# mosfet_x4.net
KiCad netlist of a schematic drawn in EAGLE
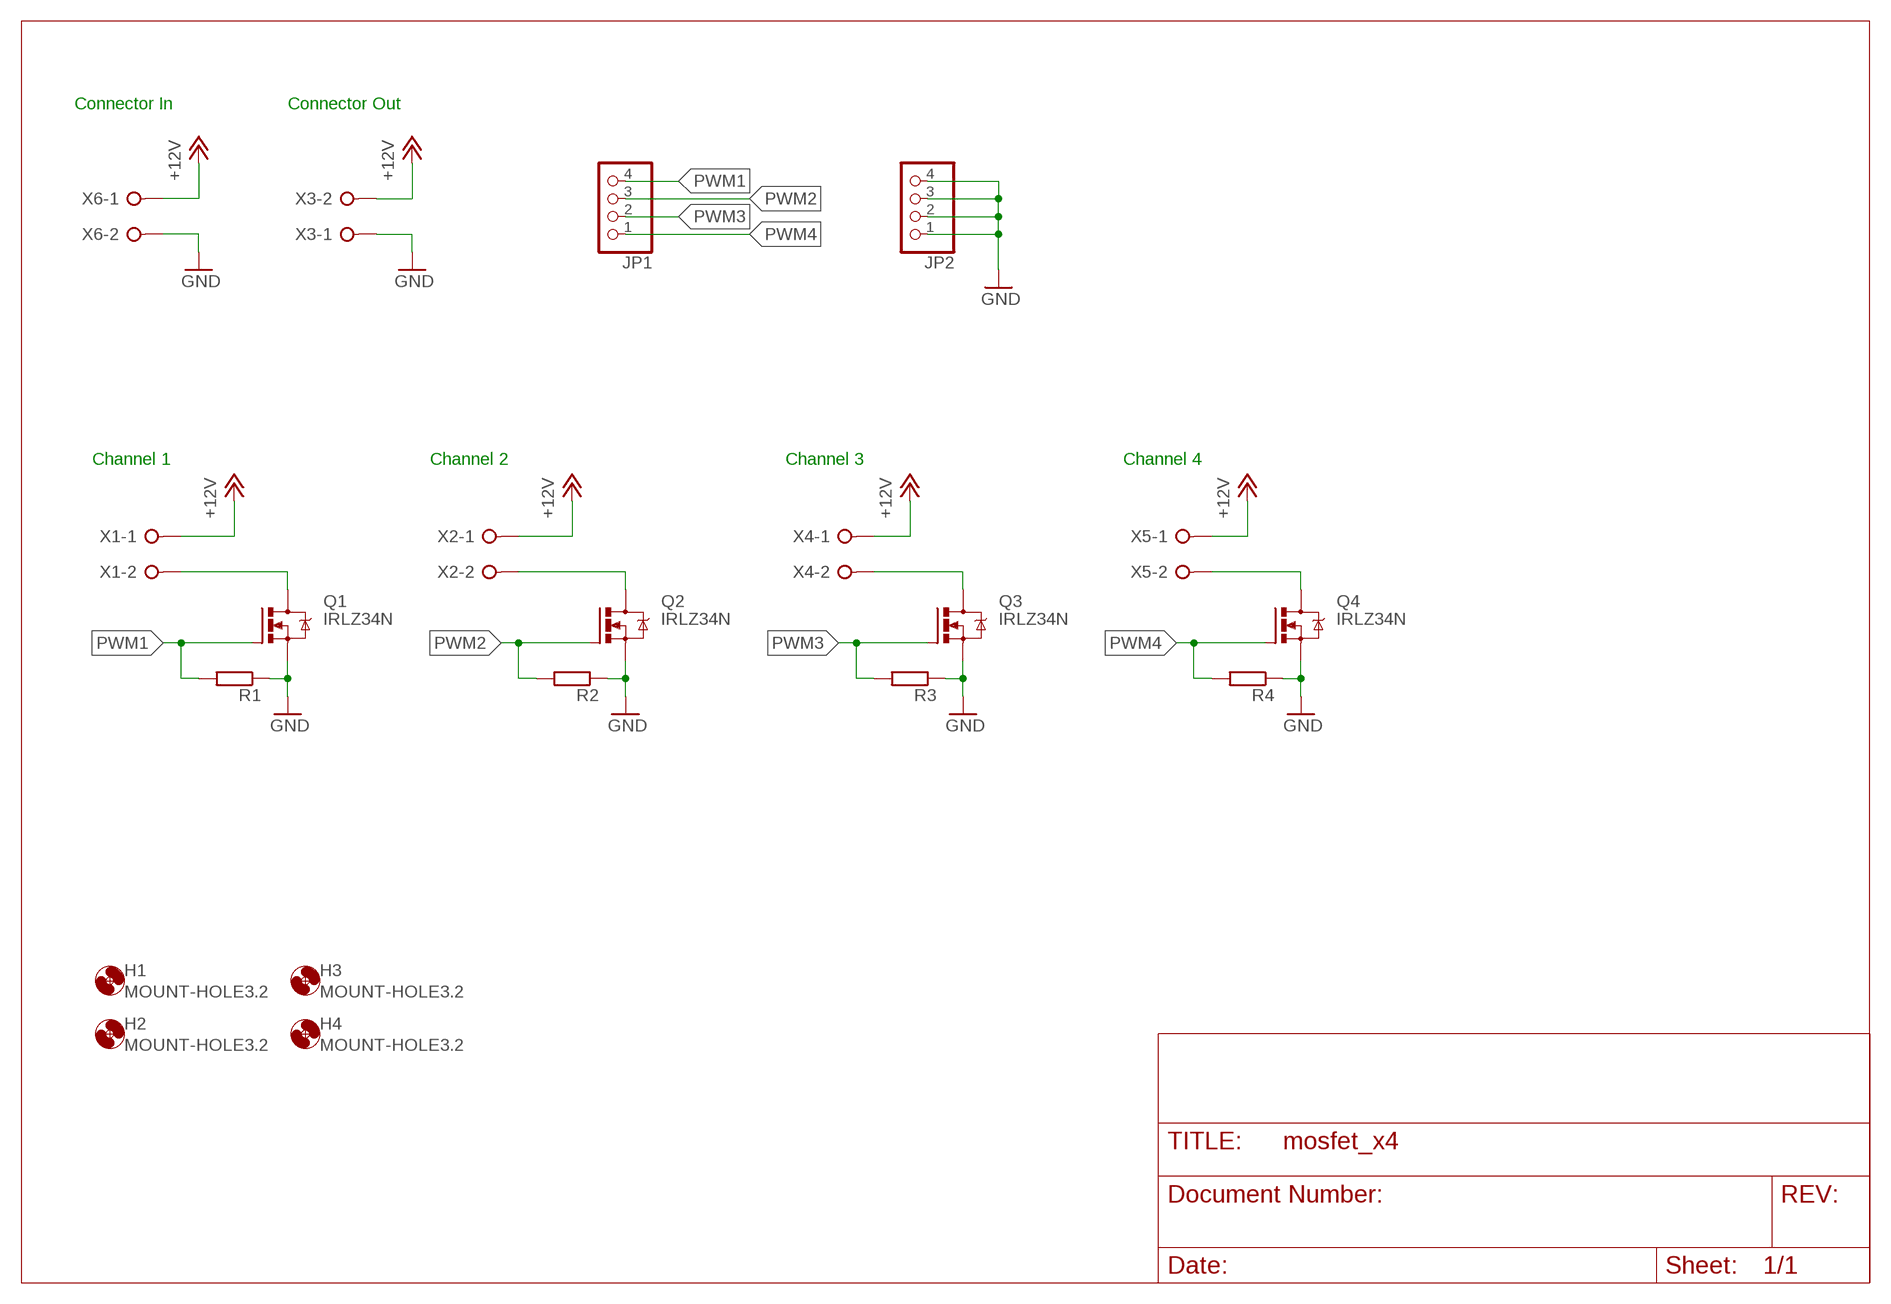
[diagram p0: schematic, sheet 1]

(export (version "E")
  (design (tool "Eeschema 10.0.6"))
  (components
    (comp (ref "H1")
      (value "MOUNT-HOLE3.2")
      (footprint "eagle-import:3,2")
      (libsource (lib "eagle-import") (part "MOUNT-HOLE3.2"))
    )
    (comp (ref "H2")
      (value "MOUNT-HOLE3.2")
      (footprint "eagle-import:3,2")
      (libsource (lib "eagle-import") (part "MOUNT-HOLE3.2"))
    )
    (comp (ref "H3")
      (value "MOUNT-HOLE3.2")
      (footprint "eagle-import:3,2")
      (libsource (lib "eagle-import") (part "MOUNT-HOLE3.2"))
    )
    (comp (ref "H4")
      (value "MOUNT-HOLE3.2")
      (footprint "eagle-import:3,2")
      (libsource (lib "eagle-import") (part "MOUNT-HOLE3.2"))
    )
    (comp (ref "JP1")
      (value "PINHD-1X4")
      (footprint "eagle-import:1X04")
      (libsource (lib "eagle-import") (part "PINHD-1X4"))
    )
    (comp (ref "JP2")
      (value "PINHD-1X4")
      (footprint "eagle-import:1X04")
      (libsource (lib "eagle-import") (part "PINHD-1X4"))
    )
    (comp (ref "Q1")
      (value "IRLZ34N")
      (footprint "eagle-import:TO220BV")
      (libsource (lib "eagle-import") (part "IRLZ44ZTO220BV"))
    )
    (comp (ref "Q2")
      (value "IRLZ34N")
      (footprint "eagle-import:TO220BV")
      (libsource (lib "eagle-import") (part "IRLZ44ZTO220BV"))
    )
    (comp (ref "Q3")
      (value "IRLZ34N")
      (footprint "eagle-import:TO220BV")
      (libsource (lib "eagle-import") (part "IRLZ44ZTO220BV"))
    )
    (comp (ref "Q4")
      (value "IRLZ34N")
      (footprint "eagle-import:TO220BV")
      (libsource (lib "eagle-import") (part "IRLZ44ZTO220BV"))
    )
    (comp (ref "R1")
      (value "R-EU_0207/10")
      (footprint "eagle-import:0207_10")
      (libsource (lib "eagle-import") (part "R-EU_0207/10"))
    )
    (comp (ref "R2")
      (value "R-EU_0207/10")
      (footprint "eagle-import:0207_10")
      (libsource (lib "eagle-import") (part "R-EU_0207/10"))
    )
    (comp (ref "R3")
      (value "R-EU_0207/10")
      (footprint "eagle-import:0207_10")
      (libsource (lib "eagle-import") (part "R-EU_0207/10"))
    )
    (comp (ref "R4")
      (value "R-EU_0207/10")
      (footprint "eagle-import:0207_10")
      (libsource (lib "eagle-import") (part "R-EU_0207/10"))
    )
    (comp (ref "X1")
      (value "W237-02P")
      (footprint "eagle-import:W237-132")
      (libsource (lib "eagle-import") (part "W237-02P"))
    )
    (comp (ref "X2")
      (value "W237-02P")
      (footprint "eagle-import:W237-132")
      (libsource (lib "eagle-import") (part "W237-02P"))
    )
    (comp (ref "X3")
      (value "W237-02P")
      (footprint "eagle-import:W237-132")
      (libsource (lib "eagle-import") (part "W237-02P"))
    )
    (comp (ref "X4")
      (value "W237-02P")
      (footprint "eagle-import:W237-132")
      (libsource (lib "eagle-import") (part "W237-02P"))
    )
    (comp (ref "X5")
      (value "W237-02P")
      (footprint "eagle-import:W237-132")
      (libsource (lib "eagle-import") (part "W237-02P"))
    )
    (comp (ref "X6")
      (value "W237-02P")
      (footprint "eagle-import:W237-132")
      (libsource (lib "eagle-import") (part "W237-02P"))
    )
  )
  (nets
    (net (code "1") (name "+12V") (class "Default")
      (node (ref "X1") (pin "1") (pinfunction "KL_1") (pintype "passive"))
      (node (ref "X2") (pin "1") (pinfunction "KL_1") (pintype "passive"))
      (node (ref "X3") (pin "2") (pinfunction "KL_2") (pintype "passive"))
      (node (ref "X4") (pin "1") (pinfunction "KL_1") (pintype "passive"))
      (node (ref "X5") (pin "1") (pinfunction "KL_1") (pintype "passive"))
      (node (ref "X6") (pin "1") (pinfunction "KL_1") (pintype "passive"))
    )
    (net (code "2") (name "GND") (class "Default")
      (node (ref "JP2") (pin "1") (pinfunction "1_1") (pintype "passive"))
      (node (ref "JP2") (pin "2") (pinfunction "2_2") (pintype "passive"))
      (node (ref "JP2") (pin "3") (pinfunction "3_3") (pintype "passive"))
      (node (ref "JP2") (pin "4") (pinfunction "4_4") (pintype "passive"))
      (node (ref "Q1") (pin "S") (pinfunction "S_S") (pintype "passive"))
      (node (ref "Q2") (pin "S") (pinfunction "S_S") (pintype "passive"))
      (node (ref "Q3") (pin "S") (pinfunction "S_S") (pintype "passive"))
      (node (ref "Q4") (pin "S") (pinfunction "S_S") (pintype "passive"))
      (node (ref "R1") (pin "1") (pinfunction "1_1") (pintype "passive"))
      (node (ref "R2") (pin "1") (pinfunction "1_1") (pintype "passive"))
      (node (ref "R3") (pin "1") (pinfunction "1_1") (pintype "passive"))
      (node (ref "R4") (pin "1") (pinfunction "1_1") (pintype "passive"))
      (node (ref "X3") (pin "1") (pinfunction "KL_1") (pintype "passive"))
      (node (ref "X6") (pin "2") (pinfunction "KL_2") (pintype "passive"))
    )
    (net (code "3") (name "Net-(X1B-KL)") (class "Default")
      (node (ref "Q1") (pin "D") (pinfunction "D_D") (pintype "passive"))
      (node (ref "X1") (pin "2") (pinfunction "KL_2") (pintype "passive"))
    )
    (net (code "4") (name "Net-(X2B-KL)") (class "Default")
      (node (ref "Q2") (pin "D") (pinfunction "D_D") (pintype "passive"))
      (node (ref "X2") (pin "2") (pinfunction "KL_2") (pintype "passive"))
    )
    (net (code "5") (name "Net-(X4B-KL)") (class "Default")
      (node (ref "Q3") (pin "D") (pinfunction "D_D") (pintype "passive"))
      (node (ref "X4") (pin "2") (pinfunction "KL_2") (pintype "passive"))
    )
    (net (code "6") (name "Net-(X5B-KL)") (class "Default")
      (node (ref "Q4") (pin "D") (pinfunction "D_D") (pintype "passive"))
      (node (ref "X5") (pin "2") (pinfunction "KL_2") (pintype "passive"))
    )
    (net (code "7") (name "PWM1") (class "Default")
      (node (ref "JP1") (pin "4") (pinfunction "4_4") (pintype "passive"))
      (node (ref "Q1") (pin "G") (pinfunction "G_G") (pintype "passive"))
      (node (ref "R1") (pin "2") (pinfunction "2_2") (pintype "passive"))
    )
    (net (code "8") (name "PWM2") (class "Default")
      (node (ref "JP1") (pin "3") (pinfunction "3_3") (pintype "passive"))
      (node (ref "Q2") (pin "G") (pinfunction "G_G") (pintype "passive"))
      (node (ref "R2") (pin "2") (pinfunction "2_2") (pintype "passive"))
    )
    (net (code "9") (name "PWM3") (class "Default")
      (node (ref "JP1") (pin "2") (pinfunction "2_2") (pintype "passive"))
      (node (ref "Q3") (pin "G") (pinfunction "G_G") (pintype "passive"))
      (node (ref "R3") (pin "2") (pinfunction "2_2") (pintype "passive"))
    )
    (net (code "10") (name "PWM4") (class "Default")
      (node (ref "JP1") (pin "1") (pinfunction "1_1") (pintype "passive"))
      (node (ref "Q4") (pin "G") (pinfunction "G_G") (pintype "passive"))
      (node (ref "R4") (pin "2") (pinfunction "2_2") (pintype "passive"))
    )
  )
)
